# wchlink.net
KiCad netlist of a schematic drawn in Altium Designer
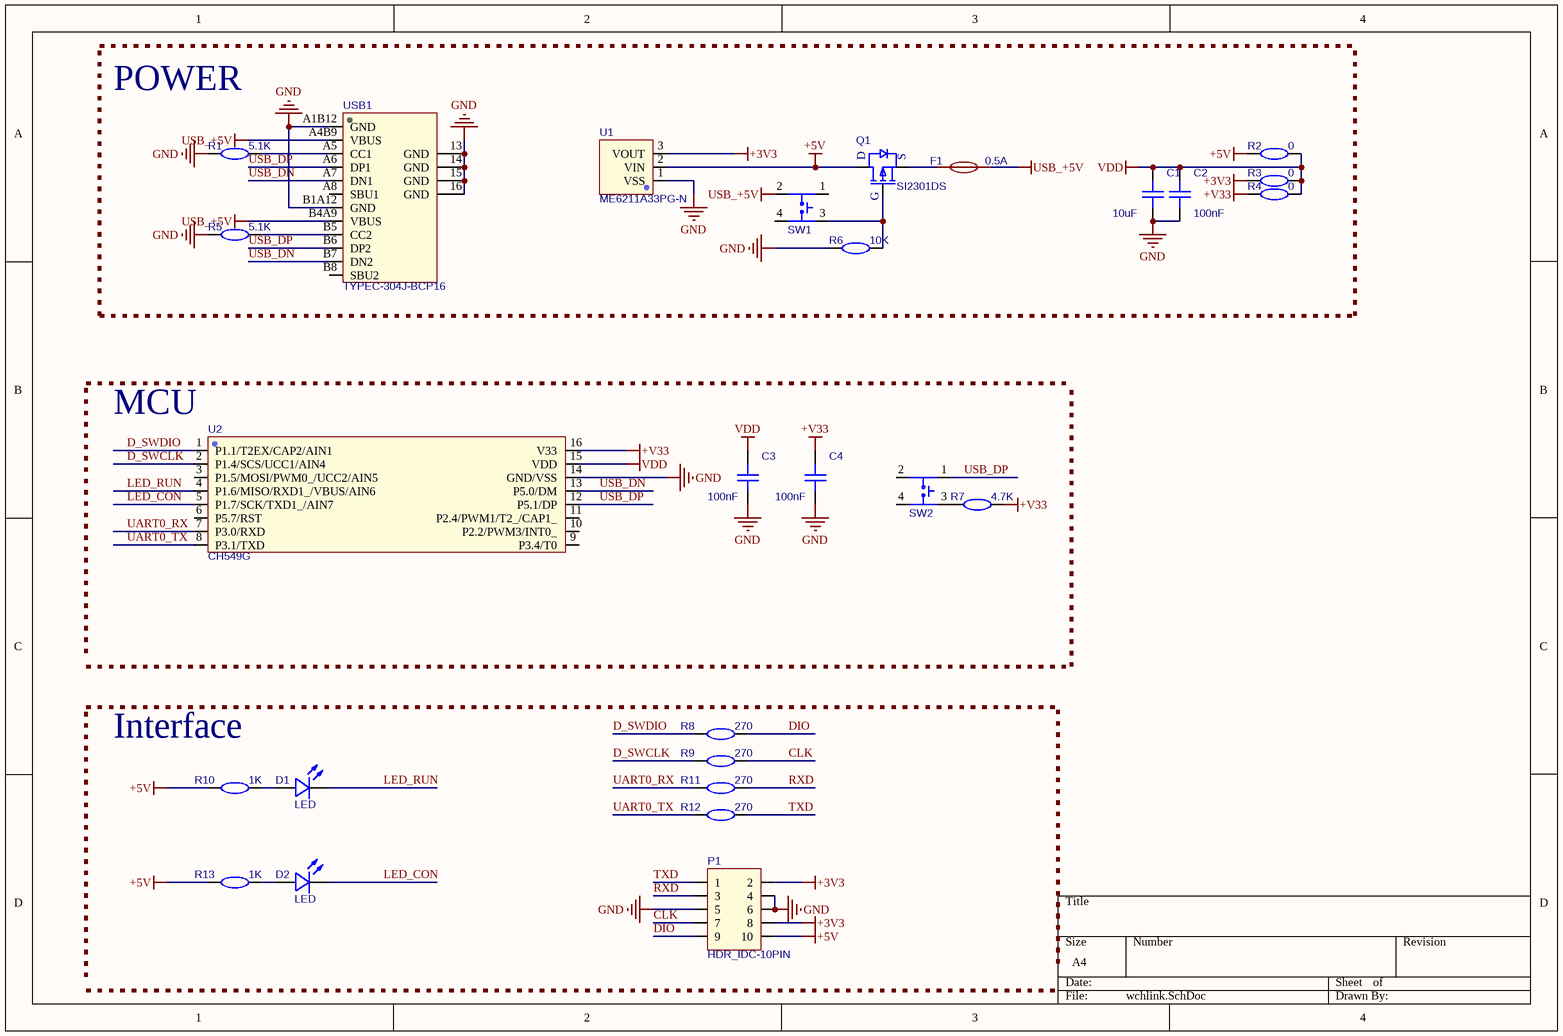
[diagram p0: wchlink.SchDoc]

(export (version "E")
  (design (tool "Eeschema 10.0.6"))
  (components
    (comp (ref "C1")
      (value "10uF")
      (footprint "C0603")
      (fields
        (field (name "BOM_SUPPLIER PART") "C325469")
        (field (name "BOM_MANUFACTURER PART") "CC0603GRNPO9BN200")
        (field (name "CONTRIBUTOR") "LCSC")
      )
      (libsource (lib "miscpcb") (part "CAP_0603"))
    )
    (comp (ref "C2")
      (value "100nF")
      (footprint "C0603")
      (fields
        (field (name "BOM_SUPPLIER PART") "C325469")
        (field (name "BOM_MANUFACTURER PART") "CC0603GRNPO9BN200")
        (field (name "CONTRIBUTOR") "LCSC")
      )
      (libsource (lib "miscpcb") (part "CAP_0603"))
    )
    (comp (ref "C3")
      (value "100nF")
      (footprint "C0603")
      (fields
        (field (name "BOM_SUPPLIER PART") "C325469")
        (field (name "BOM_MANUFACTURER PART") "CC0603GRNPO9BN200")
        (field (name "CONTRIBUTOR") "LCSC")
      )
      (libsource (lib "miscpcb") (part "CAP_0603"))
    )
    (comp (ref "C4")
      (value "100nF")
      (footprint "C0603")
      (fields
        (field (name "BOM_SUPPLIER PART") "C325469")
        (field (name "BOM_MANUFACTURER PART") "CC0603GRNPO9BN200")
        (field (name "CONTRIBUTOR") "LCSC")
      )
      (libsource (lib "miscpcb") (part "CAP_0603"))
    )
    (comp (ref "D1")
      (value "LED")
      (footprint "LED-0603")
      (fields (field (name "BOM_MANUFACTURER PART") "?"))
      (libsource (lib "miscpcb") (part "LED-Y"))
    )
    (comp (ref "D2")
      (value "LED")
      (footprint "LED-0603")
      (fields (field (name "BOM_MANUFACTURER PART") "?"))
      (libsource (lib "miscpcb") (part "LED-Y"))
    )
    (comp (ref "F1")
      (value "0.5A")
      (footprint "R0805")
      (fields
        (field (name "BOM_SUPPLIER PART") "C269104")
        (field (name "BOM_MANUFACTURER PART") "SMD0805B050TF")
        (field (name "CONTRIBUTOR") "LCSC")
      )
      (libsource (lib "altium-import") (part "root_0_0.5A_"))
    )
    (comp (ref "P1")
      (value "HDR_IDC-10PIN")
      (footprint "IDC-2X5PIN")
      (fields
        (field (name "BOM_MANUFACTURER PART") "IDC Box 2.54mm 2X5P")
        (field (name "BOM_SUPPLIER PART") "C5665")
      )
      (libsource (lib "miscpcb") (part "HDR_IDC-10PIN"))
    )
    (comp (ref "Q1")
      (value "SI2301DS")
      (footprint "SOT-23-3_L2.9-W1.3-P1.90-LS2.4-BR")
      (fields (field (name "BOM_SUPPLIER PART") "C2841444") (field (name "CONTRIBUTOR") "LCSC"))
      (libsource (lib "esp32") (part "SI2301DS"))
    )
    (comp (ref "R1")
      (value "5.1K")
      (footprint "R0603")
      (fields
        (field (name "BOM_MANUFACTURER PART") "CR0603JA0301G")
        (field (name "BOM_SUPPLIER PART") "C101323")
      )
      (libsource (lib "miscpcb") (part "RES_0603"))
    )
    (comp (ref "R2")
      (value "0")
      (footprint "R0603")
      (fields
        (field (name "BOM_MANUFACTURER PART") "CR0603JA0301G")
        (field (name "BOM_SUPPLIER PART") "C101323")
      )
      (libsource (lib "miscpcb") (part "RES_0603"))
    )
    (comp (ref "R3")
      (value "0")
      (footprint "R0603")
      (fields
        (field (name "BOM_MANUFACTURER PART") "CR0603JA0301G")
        (field (name "BOM_SUPPLIER PART") "C101323")
      )
      (libsource (lib "miscpcb") (part "RES_0603"))
    )
    (comp (ref "R4")
      (value "0")
      (footprint "R0603")
      (fields
        (field (name "BOM_MANUFACTURER PART") "CR0603JA0301G")
        (field (name "BOM_SUPPLIER PART") "C101323")
      )
      (libsource (lib "miscpcb") (part "RES_0603"))
    )
    (comp (ref "R5")
      (value "5.1K")
      (footprint "R0603")
      (fields
        (field (name "BOM_MANUFACTURER PART") "CR0603JA0301G")
        (field (name "BOM_SUPPLIER PART") "C101323")
      )
      (libsource (lib "miscpcb") (part "RES_0603"))
    )
    (comp (ref "R6")
      (value "10K")
      (footprint "R0603")
      (fields
        (field (name "BOM_MANUFACTURER PART") "CR0603JA0301G")
        (field (name "BOM_SUPPLIER PART") "C101323")
      )
      (libsource (lib "miscpcb") (part "RES_0603"))
    )
    (comp (ref "R7")
      (value "4.7K")
      (footprint "R0603")
      (fields
        (field (name "BOM_MANUFACTURER PART") "CR0603JA0301G")
        (field (name "BOM_SUPPLIER PART") "C101323")
      )
      (libsource (lib "miscpcb") (part "RES_0603"))
    )
    (comp (ref "R8")
      (value "270")
      (footprint "R0603")
      (fields
        (field (name "BOM_MANUFACTURER PART") "CR0603JA0301G")
        (field (name "BOM_SUPPLIER PART") "C101323")
      )
      (libsource (lib "miscpcb") (part "RES_0603"))
    )
    (comp (ref "R9")
      (value "270")
      (footprint "R0603")
      (fields
        (field (name "BOM_MANUFACTURER PART") "CR0603JA0301G")
        (field (name "BOM_SUPPLIER PART") "C101323")
      )
      (libsource (lib "miscpcb") (part "RES_0603"))
    )
    (comp (ref "R10")
      (value "1K")
      (footprint "R0603")
      (fields
        (field (name "BOM_MANUFACTURER PART") "CR0603JA0301G")
        (field (name "BOM_SUPPLIER PART") "C101323")
      )
      (libsource (lib "miscpcb") (part "RES_0603"))
    )
    (comp (ref "R11")
      (value "270")
      (footprint "R0603")
      (fields
        (field (name "BOM_MANUFACTURER PART") "CR0603JA0301G")
        (field (name "BOM_SUPPLIER PART") "C101323")
      )
      (libsource (lib "miscpcb") (part "RES_0603"))
    )
    (comp (ref "R12")
      (value "270")
      (footprint "R0603")
      (fields
        (field (name "BOM_MANUFACTURER PART") "CR0603JA0301G")
        (field (name "BOM_SUPPLIER PART") "C101323")
      )
      (libsource (lib "miscpcb") (part "RES_0603"))
    )
    (comp (ref "R13")
      (value "1K")
      (footprint "R0603")
      (fields
        (field (name "BOM_MANUFACTURER PART") "CR0603JA0301G")
        (field (name "BOM_SUPPLIER PART") "C101323")
      )
      (libsource (lib "miscpcb") (part "RES_0603"))
    )
    (comp (ref "SW1")
      (value "TS-1071SA-A3B3-D4")
      (footprint "KEY-SMD_4P-L3.5-W3.0-P1.40-LS4.6")
      (fields (field (name "BOM_SUPPLIER PART") "C498309") (field (name "CONTRIBUTOR") "LCSC"))
      (libsource (lib "esp32") (part "TS-1071SA-A3B3-D4"))
    )
    (comp (ref "SW2")
      (value "TS-1071SA-A3B3-D4")
      (footprint "KEY-SMD_4P-L3.5-W3.0-P1.40-LS4.6")
      (fields (field (name "BOM_SUPPLIER PART") "C498309") (field (name "CONTRIBUTOR") "LCSC"))
      (libsource (lib "esp32") (part "TS-1071SA-A3B3-D4"))
    )
    (comp (ref "U1")
      (value "ME6211A33PG-N")
      (footprint "SOT-89_L4.5-W2.5-P1.50-LS4.2-BR")
      (fields (field (name "BOM_SUPPLIER PART") "C236673") (field (name "CONTRIBUTOR") "LCSC"))
      (libsource (lib "esp32") (part "ME6211A33PG-N"))
    )
    (comp (ref "U2")
      (value "CH549G")
      (footprint "SOP-16_L10.0-W3.9-P1.27-LS6.0-BL")
      (fields (field (name "BOM_SUPPLIER PART") "C108958") (field (name "CONTRIBUTOR") "Fangbrbr"))
      (libsource (lib "miscpcb") (part "CH549G"))
    )
    (comp (ref "USB1")
      (value "TYPEC-304J-BCP16")
      (footprint "USB-C-SMD_TYPEC-304J-BCP16")
      (fields (field (name "BOM_SUPPLIER PART") "C2835315") (field (name "CONTRIBUTOR") "LCSC"))
      (libsource (lib "esp32") (part "TYPEC-304J-BCP16"))
    )
  )
  (nets
    (net (code "1") (name "+3V3") (class "Default")
      (node (ref "P1") (pin "2") (pinfunction "2_2") (pintype "passive"))
      (node (ref "P1") (pin "8") (pinfunction "8_8") (pintype "passive"))
      (node (ref "R3") (pin "2") (pinfunction "2_2") (pintype "passive"))
      (node (ref "U1") (pin "3") (pinfunction "VOUT_3") (pintype "passive"))
    )
    (net (code "2") (name "+5V") (class "Default")
      (node (ref "P1") (pin "10") (pinfunction "10_10") (pintype "passive"))
      (node (ref "Q1") (pin "3") (pinfunction "D_3") (pintype "passive"))
      (node (ref "R10") (pin "2") (pinfunction "2_2") (pintype "passive"))
      (node (ref "R13") (pin "2") (pinfunction "2_2") (pintype "passive"))
      (node (ref "R2") (pin "2") (pinfunction "2_2") (pintype "passive"))
      (node (ref "U1") (pin "2") (pinfunction "VIN_2") (pintype "passive"))
    )
    (net (code "3") (name "+V33") (class "Default")
      (node (ref "C4") (pin "2") (pinfunction "2_2") (pintype "passive"))
      (node (ref "R4") (pin "2") (pinfunction "2_2") (pintype "passive"))
      (node (ref "R7") (pin "1") (pinfunction "1_1") (pintype "passive"))
      (node (ref "U2") (pin "16") (pinfunction "V33_16") (pintype "passive"))
    )
    (net (code "4") (name "/CLK") (class "Default")
      (node (ref "P1") (pin "7") (pinfunction "7_7") (pintype "passive"))
      (node (ref "R9") (pin "1") (pinfunction "1_1") (pintype "passive"))
    )
    (net (code "5") (name "/DIO") (class "Default")
      (node (ref "P1") (pin "9") (pinfunction "9_9") (pintype "passive"))
      (node (ref "R8") (pin "1") (pinfunction "1_1") (pintype "passive"))
    )
    (net (code "6") (name "/D_SWCLK") (class "Default")
      (node (ref "R9") (pin "2") (pinfunction "2_2") (pintype "passive"))
      (node (ref "U2") (pin "2") (pinfunction "P1.4/SCS/UCC1/AIN4_2") (pintype "passive"))
    )
    (net (code "7") (name "/D_SWDIO") (class "Default")
      (node (ref "R8") (pin "2") (pinfunction "2_2") (pintype "passive"))
      (node (ref "U2") (pin "1") (pinfunction "P1.1/T2EX/CAP2/AIN1_1") (pintype "passive"))
    )
    (net (code "8") (name "/LED_CON") (class "Default")
      (node (ref "D2") (pin "2") (pinfunction "K_2") (pintype "passive"))
      (node (ref "U2") (pin "5") (pinfunction "P1.7/SCK/TXD1_/AIN7_5") (pintype "passive"))
    )
    (net (code "9") (name "/LED_RUN") (class "Default")
      (node (ref "D1") (pin "2") (pinfunction "K_2") (pintype "passive"))
      (node (ref "U2") (pin "4") (pinfunction "P1.6/MISO/RXD1_/VBUS/AIN6_4") (pintype "passive"))
    )
    (net (code "10") (name "/RXD") (class "Default")
      (node (ref "P1") (pin "3") (pinfunction "3_3") (pintype "passive"))
      (node (ref "R11") (pin "1") (pinfunction "1_1") (pintype "passive"))
    )
    (net (code "11") (name "/TXD") (class "Default")
      (node (ref "P1") (pin "1") (pinfunction "1_1") (pintype "passive"))
      (node (ref "R12") (pin "1") (pinfunction "1_1") (pintype "passive"))
    )
    (net (code "12") (name "/UART0_RX") (class "Default")
      (node (ref "R11") (pin "2") (pinfunction "2_2") (pintype "passive"))
      (node (ref "U2") (pin "7") (pinfunction "P3.0/RXD_7") (pintype "passive"))
    )
    (net (code "13") (name "/UART0_TX") (class "Default")
      (node (ref "R12") (pin "2") (pinfunction "2_2") (pintype "passive"))
      (node (ref "U2") (pin "8") (pinfunction "P3.1/TXD_8") (pintype "passive"))
    )
    (net (code "14") (name "/USB_DN") (class "Default")
      (node (ref "U2") (pin "13") (pinfunction "P5.0/DM_13") (pintype "passive"))
      (node (ref "USB1") (pin "A7") (pinfunction "DN1_A7") (pintype "passive"))
      (node (ref "USB1") (pin "B7") (pinfunction "DN2_B7") (pintype "passive"))
    )
    (net (code "15") (name "/USB_DP") (class "Default")
      (node (ref "SW2") (pin "1") (pinfunction "1_1") (pintype "passive"))
      (node (ref "U2") (pin "12") (pinfunction "P5.1/DP_12") (pintype "passive"))
      (node (ref "USB1") (pin "A6") (pinfunction "DP1_A6") (pintype "passive"))
      (node (ref "USB1") (pin "B6") (pinfunction "DP2_B6") (pintype "passive"))
    )
    (net (code "16") (name "GND") (class "Default")
      (node (ref "C1") (pin "1") (pinfunction "1_1") (pintype "passive"))
      (node (ref "C2") (pin "1") (pinfunction "1_1") (pintype "passive"))
      (node (ref "C3") (pin "1") (pinfunction "1_1") (pintype "passive"))
      (node (ref "C4") (pin "1") (pinfunction "1_1") (pintype "passive"))
      (node (ref "P1") (pin "4") (pinfunction "4_4") (pintype "passive"))
      (node (ref "P1") (pin "5") (pinfunction "5_5") (pintype "passive"))
      (node (ref "P1") (pin "6") (pinfunction "6_6") (pintype "passive"))
      (node (ref "R1") (pin "2") (pinfunction "2_2") (pintype "passive"))
      (node (ref "R5") (pin "2") (pinfunction "2_2") (pintype "passive"))
      (node (ref "R6") (pin "2") (pinfunction "2_2") (pintype "passive"))
      (node (ref "U1") (pin "1") (pinfunction "VSS_1") (pintype "passive"))
      (node (ref "U2") (pin "14") (pinfunction "GND/VSS_14") (pintype "passive"))
      (node (ref "USB1") (pin "13") (pinfunction "GND_13") (pintype "passive"))
      (node (ref "USB1") (pin "14") (pinfunction "GND_14") (pintype "passive"))
      (node (ref "USB1") (pin "15") (pinfunction "GND_15") (pintype "passive"))
      (node (ref "USB1") (pin "16") (pinfunction "GND_16") (pintype "passive"))
      (node (ref "USB1") (pin "A1B12") (pinfunction "GND_A1B12") (pintype "passive"))
      (node (ref "USB1") (pin "B1A12") (pinfunction "GND_B1A12") (pintype "passive"))
    )
    (net (code "17") (name "Net-(D1-A)") (class "Default")
      (node (ref "D1") (pin "1") (pinfunction "A_1") (pintype "passive"))
      (node (ref "R10") (pin "1") (pinfunction "1_1") (pintype "passive"))
    )
    (net (code "18") (name "Net-(D2-A)") (class "Default")
      (node (ref "D2") (pin "1") (pinfunction "A_1") (pintype "passive"))
      (node (ref "R13") (pin "1") (pinfunction "1_1") (pintype "passive"))
    )
    (net (code "19") (name "Net-(Q1-G)") (class "Default")
      (node (ref "Q1") (pin "1") (pinfunction "G_1") (pintype "passive"))
      (node (ref "R6") (pin "1") (pinfunction "1_1") (pintype "passive"))
      (node (ref "SW1") (pin "3") (pinfunction "3_3") (pintype "passive"))
    )
    (net (code "20") (name "Net-(Q1-S)") (class "Default")
      (node (ref "F1") (pin "1") (pinfunction "1_1") (pintype "passive"))
      (node (ref "Q1") (pin "2") (pinfunction "S_2") (pintype "passive"))
    )
    (net (code "21") (name "Net-(R7-Pad2)") (class "Default")
      (node (ref "R7") (pin "2") (pinfunction "2_2") (pintype "passive"))
      (node (ref "SW2") (pin "3") (pinfunction "3_3") (pintype "passive"))
    )
    (net (code "22") (name "Net-(USB1-CC1)") (class "Default")
      (node (ref "R1") (pin "1") (pinfunction "1_1") (pintype "passive"))
      (node (ref "USB1") (pin "A5") (pinfunction "CC1_A5") (pintype "passive"))
    )
    (net (code "23") (name "Net-(USB1-CC2)") (class "Default")
      (node (ref "R5") (pin "1") (pinfunction "1_1") (pintype "passive"))
      (node (ref "USB1") (pin "B5") (pinfunction "CC2_B5") (pintype "passive"))
    )
    (net (code "24") (name "USB_+5V") (class "Default")
      (node (ref "F1") (pin "2") (pinfunction "2_2") (pintype "passive"))
      (node (ref "SW1") (pin "2") (pinfunction "2_2") (pintype "passive"))
      (node (ref "USB1") (pin "A4B9") (pinfunction "VBUS_A4B9") (pintype "passive"))
      (node (ref "USB1") (pin "B4A9") (pinfunction "VBUS_B4A9") (pintype "passive"))
    )
    (net (code "25") (name "VDD") (class "Default")
      (node (ref "C1") (pin "2") (pinfunction "2_2") (pintype "passive"))
      (node (ref "C2") (pin "2") (pinfunction "2_2") (pintype "passive"))
      (node (ref "C3") (pin "2") (pinfunction "2_2") (pintype "passive"))
      (node (ref "R2") (pin "1") (pinfunction "1_1") (pintype "passive"))
      (node (ref "R3") (pin "1") (pinfunction "1_1") (pintype "passive"))
      (node (ref "R4") (pin "1") (pinfunction "1_1") (pintype "passive"))
      (node (ref "U2") (pin "15") (pinfunction "VDD_15") (pintype "passive"))
    )
    (net (code "26") (name "unconnected-(SW1-Pad1)") (class "Default")
      (node (ref "SW1") (pin "1") (pinfunction "1_1") (pintype "passive"))
    )
    (net (code "27") (name "unconnected-(SW1-Pad4)") (class "Default")
      (node (ref "SW1") (pin "4") (pinfunction "4_4") (pintype "passive"))
    )
    (net (code "28") (name "unconnected-(SW2-Pad2)") (class "Default")
      (node (ref "SW2") (pin "2") (pinfunction "2_2") (pintype "passive"))
    )
    (net (code "29") (name "unconnected-(SW2-Pad4)") (class "Default")
      (node (ref "SW2") (pin "4") (pinfunction "4_4") (pintype "passive"))
    )
    (net (code "30") (name "unconnected-(U2-P1.5{slash}MOSI{slash}PWM0_{slash}UCC2{slash}AIN5-Pad3)") (class "Default")
      (node (ref "U2") (pin "3") (pinfunction "P1.5/MOSI/PWM0_/UCC2/AIN5_3") (pintype "passive"))
    )
    (net (code "31") (name "unconnected-(U2-P2.2{slash}PWM3{slash}INT0_-Pad10)") (class "Default")
      (node (ref "U2") (pin "10") (pinfunction "P2.2/PWM3/INT0__10") (pintype "passive"))
    )
    (net (code "32") (name "unconnected-(U2-P2.4{slash}PWM1{slash}T2_{slash}CAP1_-Pad11)") (class "Default")
      (node (ref "U2") (pin "11") (pinfunction "P2.4/PWM1/T2_/CAP1__11") (pintype "passive"))
    )
    (net (code "33") (name "unconnected-(U2-P3.4{slash}T0-Pad9)") (class "Default")
      (node (ref "U2") (pin "9") (pinfunction "P3.4/T0_9") (pintype "passive"))
    )
    (net (code "34") (name "unconnected-(U2-P5.7{slash}RST-Pad6)") (class "Default")
      (node (ref "U2") (pin "6") (pinfunction "P5.7/RST_6") (pintype "passive"))
    )
    (net (code "35") (name "unconnected-(USB1-SBU1-PadA8)") (class "Default")
      (node (ref "USB1") (pin "A8") (pinfunction "SBU1_A8") (pintype "passive"))
    )
    (net (code "36") (name "unconnected-(USB1-SBU2-PadB8)") (class "Default")
      (node (ref "USB1") (pin "B8") (pinfunction "SBU2_B8") (pintype "passive"))
    )
  )
)
